# puente_h.net
KiCad netlist of a schematic drawn in EAGLE
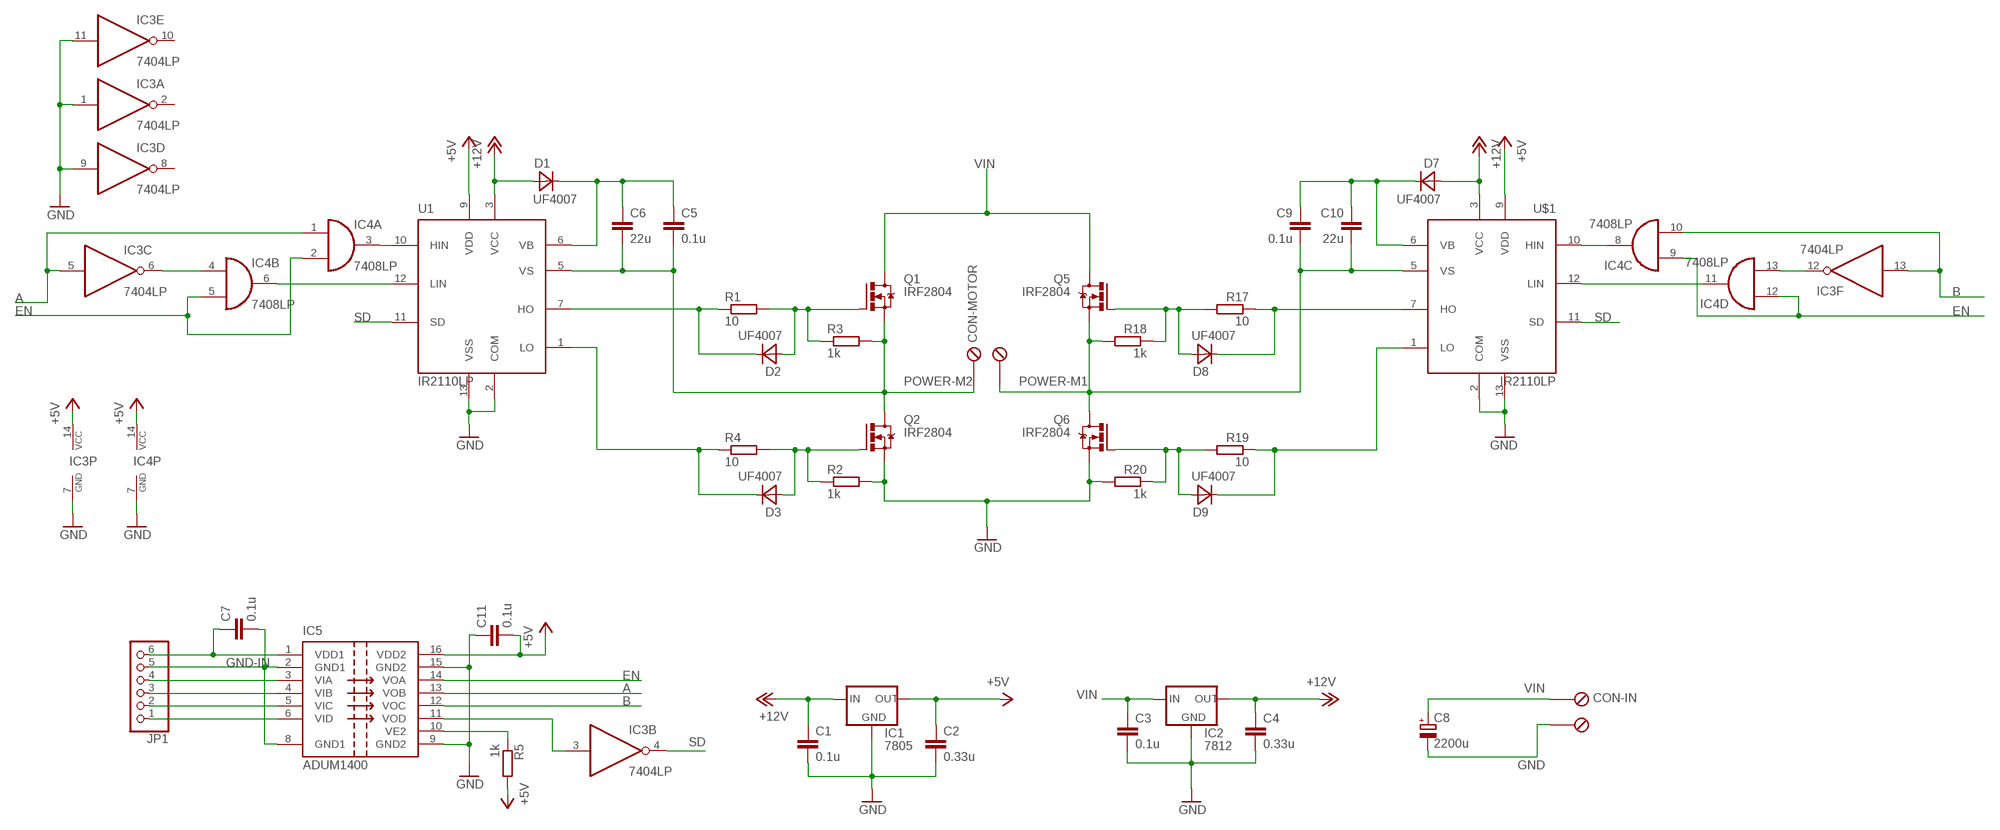
[diagram p0: schematic, sheet 1]

(export (version "E")
  (design (tool "Eeschema 10.0.6"))
  (components
    (comp (ref "C1")
      (value "0.1u")
      (footprint "eagle-import:C050-025X075")
      (libsource (lib "eagle-import") (part "C-EU050-025X075"))
    )
    (comp (ref "C2")
      (value "0.33u")
      (footprint "eagle-import:C025-025X050")
      (libsource (lib "eagle-import") (part "C-EU025-025X050"))
    )
    (comp (ref "C3")
      (value "0.1u")
      (footprint "eagle-import:C050-025X075")
      (libsource (lib "eagle-import") (part "C-EU050-025X075"))
    )
    (comp (ref "C4")
      (value "0.33u")
      (footprint "eagle-import:C025-025X050")
      (libsource (lib "eagle-import") (part "C-EU025-025X050"))
    )
    (comp (ref "C5")
      (value "0.1u")
      (footprint "eagle-import:C050-025X075")
      (libsource (lib "eagle-import") (part "C-EU050-025X075"))
    )
    (comp (ref "C6")
      (value "22u")
      (footprint "eagle-import:C025-025X050")
      (libsource (lib "eagle-import") (part "C-EU025-025X050"))
    )
    (comp (ref "C7")
      (value "0.1u")
      (footprint "eagle-import:C3216")
      (libsource (lib "eagle-import") (part "C-EUC3216"))
    )
    (comp (ref "C8")
      (value "2200u")
      (footprint "eagle-import:E7,5-16")
      (libsource (lib "eagle-import") (part "CPOL-EUE7.5-16"))
    )
    (comp (ref "C9")
      (value "0.1u")
      (footprint "eagle-import:C050-025X075")
      (libsource (lib "eagle-import") (part "C-EU050-025X075"))
    )
    (comp (ref "C10")
      (value "22u")
      (footprint "eagle-import:C025-025X050")
      (libsource (lib "eagle-import") (part "C-EU025-025X050"))
    )
    (comp (ref "C11")
      (value "0.1u")
      (footprint "eagle-import:C3216")
      (libsource (lib "eagle-import") (part "C-EUC3216"))
    )
    (comp (ref "CON-IN")
      (value "METALTEX-2")
      (footprint "eagle-import:METALTEX-2")
      (libsource (lib "eagle-import") (part "METALTEX-2"))
    )
    (comp (ref "CON-MOTOR")
      (value "METALTEX-2")
      (footprint "eagle-import:METALTEX-2")
      (libsource (lib "eagle-import") (part "METALTEX-2"))
    )
    (comp (ref "D1")
      (value "UF4007")
      (footprint "eagle-import:UF4007")
      (libsource (lib "eagle-import") (part "UF4007"))
    )
    (comp (ref "D2")
      (value "UF4007")
      (footprint "eagle-import:UF4007")
      (libsource (lib "eagle-import") (part "UF4007"))
    )
    (comp (ref "D3")
      (value "UF4007")
      (footprint "eagle-import:UF4007")
      (libsource (lib "eagle-import") (part "UF4007"))
    )
    (comp (ref "D7")
      (value "UF4007")
      (footprint "eagle-import:UF4007")
      (libsource (lib "eagle-import") (part "UF4007"))
    )
    (comp (ref "D8")
      (value "UF4007")
      (footprint "eagle-import:UF4007")
      (libsource (lib "eagle-import") (part "UF4007"))
    )
    (comp (ref "D9")
      (value "UF4007")
      (footprint "eagle-import:UF4007")
      (libsource (lib "eagle-import") (part "UF4007"))
    )
    (comp (ref "IC1")
      (value "7805")
      (footprint "eagle-import:78XXS")
      (libsource (lib "eagle-import") (part "78XXS"))
    )
    (comp (ref "IC2")
      (value "7812")
      (footprint "eagle-import:78XXS")
      (libsource (lib "eagle-import") (part "78XXS"))
    )
    (comp (ref "IC3")
      (value "7404LP")
      (footprint "eagle-import:IR2110-LP")
      (libsource (lib "eagle-import") (part "7404LP"))
    )
    (comp (ref "IC4")
      (value "7408LP")
      (footprint "eagle-import:IR2110-LP")
      (libsource (lib "eagle-import") (part "7408LP"))
    )
    (comp (ref "IC5")
      (value "ADUM1400")
      (footprint "eagle-import:SO16W")
      (libsource (lib "eagle-import") (part "ADUM1400"))
    )
    (comp (ref "JP1")
      (value "PINHD-1X6")
      (footprint "eagle-import:1X06")
      (libsource (lib "eagle-import") (part "PINHD-1X6"))
    )
    (comp (ref "Q1")
      (value "IRF2804")
      (footprint "eagle-import:IRF2804")
      (libsource (lib "eagle-import") (part "IRF2804"))
    )
    (comp (ref "Q2")
      (value "IRF2804")
      (footprint "eagle-import:IRF2804")
      (libsource (lib "eagle-import") (part "IRF2804"))
    )
    (comp (ref "Q5")
      (value "IRF2804")
      (footprint "eagle-import:IRF2804")
      (libsource (lib "eagle-import") (part "IRF2804"))
    )
    (comp (ref "Q6")
      (value "IRF2804")
      (footprint "eagle-import:IRF2804")
      (libsource (lib "eagle-import") (part "IRF2804"))
    )
    (comp (ref "R1")
      (value "10")
      (footprint "eagle-import:0207_12")
      (libsource (lib "eagle-import") (part "R-EU_0207/12"))
    )
    (comp (ref "R2")
      (value "1k")
      (footprint "eagle-import:0207_12")
      (libsource (lib "eagle-import") (part "R-EU_0207/12"))
    )
    (comp (ref "R3")
      (value "1k")
      (footprint "eagle-import:0207_12")
      (libsource (lib "eagle-import") (part "R-EU_0207/12"))
    )
    (comp (ref "R4")
      (value "10")
      (footprint "eagle-import:0207_12")
      (libsource (lib "eagle-import") (part "R-EU_0207/12"))
    )
    (comp (ref "R5")
      (value "1k")
      (footprint "eagle-import:0207_12")
      (libsource (lib "eagle-import") (part "R-EU_0207/12"))
    )
    (comp (ref "R17")
      (value "10")
      (footprint "eagle-import:0207_12")
      (libsource (lib "eagle-import") (part "R-EU_0207/12"))
    )
    (comp (ref "R18")
      (value "1k")
      (footprint "eagle-import:0207_12")
      (libsource (lib "eagle-import") (part "R-EU_0207/12"))
    )
    (comp (ref "R19")
      (value "10")
      (footprint "eagle-import:0207_12")
      (libsource (lib "eagle-import") (part "R-EU_0207/12"))
    )
    (comp (ref "R20")
      (value "1k")
      (footprint "eagle-import:0207_12")
      (libsource (lib "eagle-import") (part "R-EU_0207/12"))
    )
    (comp (ref "U$1")
      (value "IR2110LP")
      (footprint "eagle-import:IR2110-LP")
      (libsource (lib "eagle-import") (part "IR2110LP"))
    )
    (comp (ref "U1")
      (value "IR2110LP")
      (footprint "eagle-import:IR2110-LP")
      (libsource (lib "eagle-import") (part "IR2110LP"))
    )
  )
  (nets
    (net (code "1") (name "+5V") (class "Default")
      (node (ref "C11") (pin "2") (pinfunction "2_2") (pintype "passive"))
      (node (ref "C2") (pin "1") (pinfunction "1_1") (pintype "passive"))
      (node (ref "IC1") (pin "OUT") (pinfunction "OUT_OUT") (pintype "passive"))
      (node (ref "IC3") (pin "14") (pinfunction "VCC_14") (pintype "power_in"))
      (node (ref "IC4") (pin "14") (pinfunction "VCC_14") (pintype "power_in"))
      (node (ref "IC5") (pin "16") (pinfunction "VDD2_16") (pintype "power_in"))
      (node (ref "R5") (pin "2") (pinfunction "2_2") (pintype "passive"))
      (node (ref "U$1") (pin "9") (pinfunction "VDD_9") (pintype "power_in"))
      (node (ref "U1") (pin "9") (pinfunction "VDD_9") (pintype "power_in"))
    )
    (net (code "2") (name "+12V") (class "Default")
      (node (ref "C1") (pin "1") (pinfunction "1_1") (pintype "passive"))
      (node (ref "C4") (pin "1") (pinfunction "1_1") (pintype "passive"))
      (node (ref "D1") (pin "A") (pinfunction "A_A") (pintype "passive"))
      (node (ref "D7") (pin "A") (pinfunction "A_A") (pintype "passive"))
      (node (ref "IC1") (pin "IN") (pinfunction "IN_IN") (pintype "input"))
      (node (ref "IC2") (pin "OUT") (pinfunction "OUT_OUT") (pintype "passive"))
      (node (ref "U$1") (pin "3") (pinfunction "VCC_3") (pintype "power_in"))
      (node (ref "U1") (pin "3") (pinfunction "VCC_3") (pintype "power_in"))
    )
    (net (code "3") (name "/A") (class "Default")
      (node (ref "IC3") (pin "5") (pinfunction "I_5") (pintype "input"))
      (node (ref "IC4") (pin "1") (pinfunction "I0_1") (pintype "input"))
      (node (ref "IC5") (pin "13") (pinfunction "VOB_13") (pintype "output"))
    )
    (net (code "4") (name "/B") (class "Default")
      (node (ref "IC3") (pin "13") (pinfunction "I_13") (pintype "input"))
      (node (ref "IC4") (pin "10") (pinfunction "I1_10") (pintype "input"))
      (node (ref "IC5") (pin "12") (pinfunction "VOC_12") (pintype "output"))
    )
    (net (code "5") (name "/EN") (class "Default")
      (node (ref "IC4") (pin "12") (pinfunction "I0_12") (pintype "input"))
      (node (ref "IC4") (pin "2") (pinfunction "I1_2") (pintype "input"))
      (node (ref "IC4") (pin "5") (pinfunction "I1_5") (pintype "input"))
      (node (ref "IC4") (pin "9") (pinfunction "I0_9") (pintype "input"))
      (node (ref "IC5") (pin "14") (pinfunction "VOA_14") (pintype "output"))
    )
    (net (code "6") (name "/GND-IN") (class "Default")
      (node (ref "C7") (pin "2") (pinfunction "2_2") (pintype "passive"))
      (node (ref "IC5") (pin "2") (pinfunction "GND1_2") (pintype "power_in"))
      (node (ref "IC5") (pin "8") (pinfunction "GND1_8") (pintype "power_in"))
      (node (ref "JP1") (pin "5") (pinfunction "5_5") (pintype "passive"))
    )
    (net (code "7") (name "/POWER-M1") (class "Default")
      (node (ref "C10") (pin "2") (pinfunction "2_2") (pintype "passive"))
      (node (ref "C9") (pin "2") (pinfunction "2_2") (pintype "passive"))
      (node (ref "CON-MOTOR") (pin "P2") (pinfunction "P2_P2") (pintype "bidirectional"))
      (node (ref "Q5") (pin "S") (pinfunction "S_S") (pintype "passive"))
      (node (ref "Q6") (pin "D") (pinfunction "D_D") (pintype "passive"))
      (node (ref "R18") (pin "2") (pinfunction "2_2") (pintype "passive"))
      (node (ref "U$1") (pin "5") (pinfunction "VS_5") (pintype "power_in"))
    )
    (net (code "8") (name "/POWER-M2") (class "Default")
      (node (ref "C5") (pin "2") (pinfunction "2_2") (pintype "passive"))
      (node (ref "C6") (pin "2") (pinfunction "2_2") (pintype "passive"))
      (node (ref "CON-MOTOR") (pin "P1") (pinfunction "P1_P1") (pintype "bidirectional"))
      (node (ref "Q1") (pin "S") (pinfunction "S_S") (pintype "passive"))
      (node (ref "Q2") (pin "D") (pinfunction "D_D") (pintype "passive"))
      (node (ref "R3") (pin "2") (pinfunction "2_2") (pintype "passive"))
      (node (ref "U1") (pin "5") (pinfunction "VS_5") (pintype "power_in"))
    )
    (net (code "9") (name "/SD") (class "Default")
      (node (ref "IC3") (pin "4") (pinfunction "O_4") (pintype "output"))
      (node (ref "U$1") (pin "11") (pinfunction "SD_11") (pintype "input"))
      (node (ref "U1") (pin "11") (pinfunction "SD_11") (pintype "input"))
    )
    (net (code "10") (name "/VIN") (class "Default")
      (node (ref "C3") (pin "1") (pinfunction "1_1") (pintype "passive"))
      (node (ref "C8") (pin "+") (pinfunction "+_+") (pintype "passive"))
      (node (ref "CON-IN") (pin "P1") (pinfunction "P1_P1") (pintype "bidirectional"))
      (node (ref "IC2") (pin "IN") (pinfunction "IN_IN") (pintype "input"))
      (node (ref "Q1") (pin "D") (pinfunction "D_D") (pintype "passive"))
      (node (ref "Q5") (pin "D") (pinfunction "D_D") (pintype "passive"))
    )
    (net (code "11") (name "GND") (class "Default")
      (node (ref "C1") (pin "2") (pinfunction "2_2") (pintype "passive"))
      (node (ref "C11") (pin "1") (pinfunction "1_1") (pintype "passive"))
      (node (ref "C2") (pin "2") (pinfunction "2_2") (pintype "passive"))
      (node (ref "C3") (pin "2") (pinfunction "2_2") (pintype "passive"))
      (node (ref "C4") (pin "2") (pinfunction "2_2") (pintype "passive"))
      (node (ref "C8") (pin "-") (pinfunction "-_-") (pintype "passive"))
      (node (ref "CON-IN") (pin "P2") (pinfunction "P2_P2") (pintype "bidirectional"))
      (node (ref "IC1") (pin "GND") (pinfunction "GND_GND") (pintype "input"))
      (node (ref "IC2") (pin "GND") (pinfunction "GND_GND") (pintype "input"))
      (node (ref "IC3") (pin "1") (pinfunction "I_1") (pintype "input"))
      (node (ref "IC3") (pin "11") (pinfunction "I_11") (pintype "input"))
      (node (ref "IC3") (pin "7") (pinfunction "GND_7") (pintype "power_in"))
      (node (ref "IC3") (pin "9") (pinfunction "I_9") (pintype "input"))
      (node (ref "IC4") (pin "7") (pinfunction "GND_7") (pintype "power_in"))
      (node (ref "IC5") (pin "15") (pinfunction "GND2_15") (pintype "power_in"))
      (node (ref "IC5") (pin "9") (pinfunction "GND2_9") (pintype "power_in"))
      (node (ref "Q2") (pin "S") (pinfunction "S_S") (pintype "passive"))
      (node (ref "Q6") (pin "S") (pinfunction "S_S") (pintype "passive"))
      (node (ref "R2") (pin "2") (pinfunction "2_2") (pintype "passive"))
      (node (ref "R20") (pin "2") (pinfunction "2_2") (pintype "passive"))
      (node (ref "U$1") (pin "13") (pinfunction "VSS_13") (pintype "power_in"))
      (node (ref "U$1") (pin "2") (pinfunction "COM_2") (pintype "power_in"))
      (node (ref "U1") (pin "13") (pinfunction "VSS_13") (pintype "power_in"))
      (node (ref "U1") (pin "2") (pinfunction "COM_2") (pintype "power_in"))
    )
    (net (code "12") (name "Net-(D2-PadA)") (class "Default")
      (node (ref "D2") (pin "A") (pinfunction "A_A") (pintype "passive"))
      (node (ref "Q1") (pin "G") (pinfunction "G_G") (pintype "passive"))
      (node (ref "R1") (pin "2") (pinfunction "2_2") (pintype "passive"))
      (node (ref "R3") (pin "1") (pinfunction "1_1") (pintype "passive"))
    )
    (net (code "13") (name "Net-(D3-PadA)") (class "Default")
      (node (ref "D3") (pin "A") (pinfunction "A_A") (pintype "passive"))
      (node (ref "Q2") (pin "G") (pinfunction "G_G") (pintype "passive"))
      (node (ref "R2") (pin "1") (pinfunction "1_1") (pintype "passive"))
      (node (ref "R4") (pin "2") (pinfunction "2_2") (pintype "passive"))
    )
    (net (code "14") (name "Net-(D8-PadA)") (class "Default")
      (node (ref "D8") (pin "A") (pinfunction "A_A") (pintype "passive"))
      (node (ref "Q5") (pin "G") (pinfunction "G_G") (pintype "passive"))
      (node (ref "R17") (pin "2") (pinfunction "2_2") (pintype "passive"))
      (node (ref "R18") (pin "1") (pinfunction "1_1") (pintype "passive"))
    )
    (net (code "15") (name "Net-(D9-PadA)") (class "Default")
      (node (ref "D9") (pin "A") (pinfunction "A_A") (pintype "passive"))
      (node (ref "Q6") (pin "G") (pinfunction "G_G") (pintype "passive"))
      (node (ref "R19") (pin "2") (pinfunction "2_2") (pintype "passive"))
      (node (ref "R20") (pin "1") (pinfunction "1_1") (pintype "passive"))
    )
    (net (code "16") (name "Net-(IC3B-I)") (class "Default")
      (node (ref "IC3") (pin "3") (pinfunction "I_3") (pintype "input"))
      (node (ref "IC5") (pin "11") (pinfunction "VOD_11") (pintype "output"))
    )
    (net (code "17") (name "Net-(IC3C-O)") (class "Default")
      (node (ref "IC3") (pin "6") (pinfunction "O_6") (pintype "output"))
      (node (ref "IC4") (pin "4") (pinfunction "I0_4") (pintype "input"))
    )
    (net (code "18") (name "Net-(IC3F-O)") (class "Default")
      (node (ref "IC3") (pin "12") (pinfunction "O_12") (pintype "output"))
      (node (ref "IC4") (pin "13") (pinfunction "I1_13") (pintype "input"))
    )
    (net (code "19") (name "Net-(IC4A-O)") (class "Default")
      (node (ref "IC4") (pin "3") (pinfunction "O_3") (pintype "output"))
      (node (ref "U1") (pin "10") (pinfunction "HIN_10") (pintype "input"))
    )
    (net (code "20") (name "Net-(IC4B-O)") (class "Default")
      (node (ref "IC4") (pin "6") (pinfunction "O_6") (pintype "output"))
      (node (ref "U1") (pin "12") (pinfunction "LIN_12") (pintype "input"))
    )
    (net (code "21") (name "Net-(IC4C-O)") (class "Default")
      (node (ref "IC4") (pin "8") (pinfunction "O_8") (pintype "output"))
      (node (ref "U$1") (pin "10") (pinfunction "HIN_10") (pintype "input"))
    )
    (net (code "22") (name "Net-(IC4D-O)") (class "Default")
      (node (ref "IC4") (pin "11") (pinfunction "O_11") (pintype "output"))
      (node (ref "U$1") (pin "12") (pinfunction "LIN_12") (pintype "input"))
    )
    (net (code "23") (name "Net-(IC5-VDD1)") (class "Default")
      (node (ref "C7") (pin "1") (pinfunction "1_1") (pintype "passive"))
      (node (ref "IC5") (pin "1") (pinfunction "VDD1_1") (pintype "power_in"))
      (node (ref "JP1") (pin "6") (pinfunction "6_6") (pintype "passive"))
    )
    (net (code "24") (name "Net-(IC5-VE2)") (class "Default")
      (node (ref "IC5") (pin "10") (pinfunction "VE2_10") (pintype "passive"))
      (node (ref "R5") (pin "1") (pinfunction "1_1") (pintype "passive"))
    )
    (net (code "25") (name "Net-(IC5-VIA)") (class "Default")
      (node (ref "IC5") (pin "3") (pinfunction "VIA_3") (pintype "input"))
      (node (ref "JP1") (pin "4") (pinfunction "4_4") (pintype "passive"))
    )
    (net (code "26") (name "Net-(IC5-VIB)") (class "Default")
      (node (ref "IC5") (pin "4") (pinfunction "VIB_4") (pintype "input"))
      (node (ref "JP1") (pin "3") (pinfunction "3_3") (pintype "passive"))
    )
    (net (code "27") (name "Net-(IC5-VIC)") (class "Default")
      (node (ref "IC5") (pin "5") (pinfunction "VIC_5") (pintype "input"))
      (node (ref "JP1") (pin "2") (pinfunction "2_2") (pintype "passive"))
    )
    (net (code "28") (name "Net-(IC5-VID)") (class "Default")
      (node (ref "IC5") (pin "6") (pinfunction "VID_6") (pintype "input"))
      (node (ref "JP1") (pin "1") (pinfunction "1_1") (pintype "passive"))
    )
    (net (code "29") (name "Net-(U$1-HO)") (class "Default")
      (node (ref "D8") (pin "C") (pinfunction "C_C") (pintype "passive"))
      (node (ref "R17") (pin "1") (pinfunction "1_1") (pintype "passive"))
      (node (ref "U$1") (pin "7") (pinfunction "HO_7") (pintype "output"))
    )
    (net (code "30") (name "Net-(U$1-LO)") (class "Default")
      (node (ref "D9") (pin "C") (pinfunction "C_C") (pintype "passive"))
      (node (ref "R19") (pin "1") (pinfunction "1_1") (pintype "passive"))
      (node (ref "U$1") (pin "1") (pinfunction "LO_1") (pintype "output"))
    )
    (net (code "31") (name "Net-(U$1-VB)") (class "Default")
      (node (ref "C10") (pin "1") (pinfunction "1_1") (pintype "passive"))
      (node (ref "C9") (pin "1") (pinfunction "1_1") (pintype "passive"))
      (node (ref "D7") (pin "C") (pinfunction "C_C") (pintype "passive"))
      (node (ref "U$1") (pin "6") (pinfunction "VB_6") (pintype "power_in"))
    )
    (net (code "32") (name "Net-(U1-HO)") (class "Default")
      (node (ref "D2") (pin "C") (pinfunction "C_C") (pintype "passive"))
      (node (ref "R1") (pin "1") (pinfunction "1_1") (pintype "passive"))
      (node (ref "U1") (pin "7") (pinfunction "HO_7") (pintype "output"))
    )
    (net (code "33") (name "Net-(U1-LO)") (class "Default")
      (node (ref "D3") (pin "C") (pinfunction "C_C") (pintype "passive"))
      (node (ref "R4") (pin "1") (pinfunction "1_1") (pintype "passive"))
      (node (ref "U1") (pin "1") (pinfunction "LO_1") (pintype "output"))
    )
    (net (code "34") (name "Net-(U1-VB)") (class "Default")
      (node (ref "C5") (pin "1") (pinfunction "1_1") (pintype "passive"))
      (node (ref "C6") (pin "1") (pinfunction "1_1") (pintype "passive"))
      (node (ref "D1") (pin "C") (pinfunction "C_C") (pintype "passive"))
      (node (ref "U1") (pin "6") (pinfunction "VB_6") (pintype "power_in"))
    )
    (net (code "35") (name "unconnected-(IC3A-O-Pad2)") (class "Default")
      (node (ref "IC3") (pin "2") (pinfunction "O_2") (pintype "output"))
    )
    (net (code "36") (name "unconnected-(IC3D-O-Pad8)") (class "Default")
      (node (ref "IC3") (pin "8") (pinfunction "O_8") (pintype "output"))
    )
    (net (code "37") (name "unconnected-(IC3E-O-Pad10)") (class "Default")
      (node (ref "IC3") (pin "10") (pinfunction "O_10") (pintype "output"))
    )
  )
)
